# Speed_Bag_Counter-v10.net
KiCad netlist of a schematic drawn in EAGLE
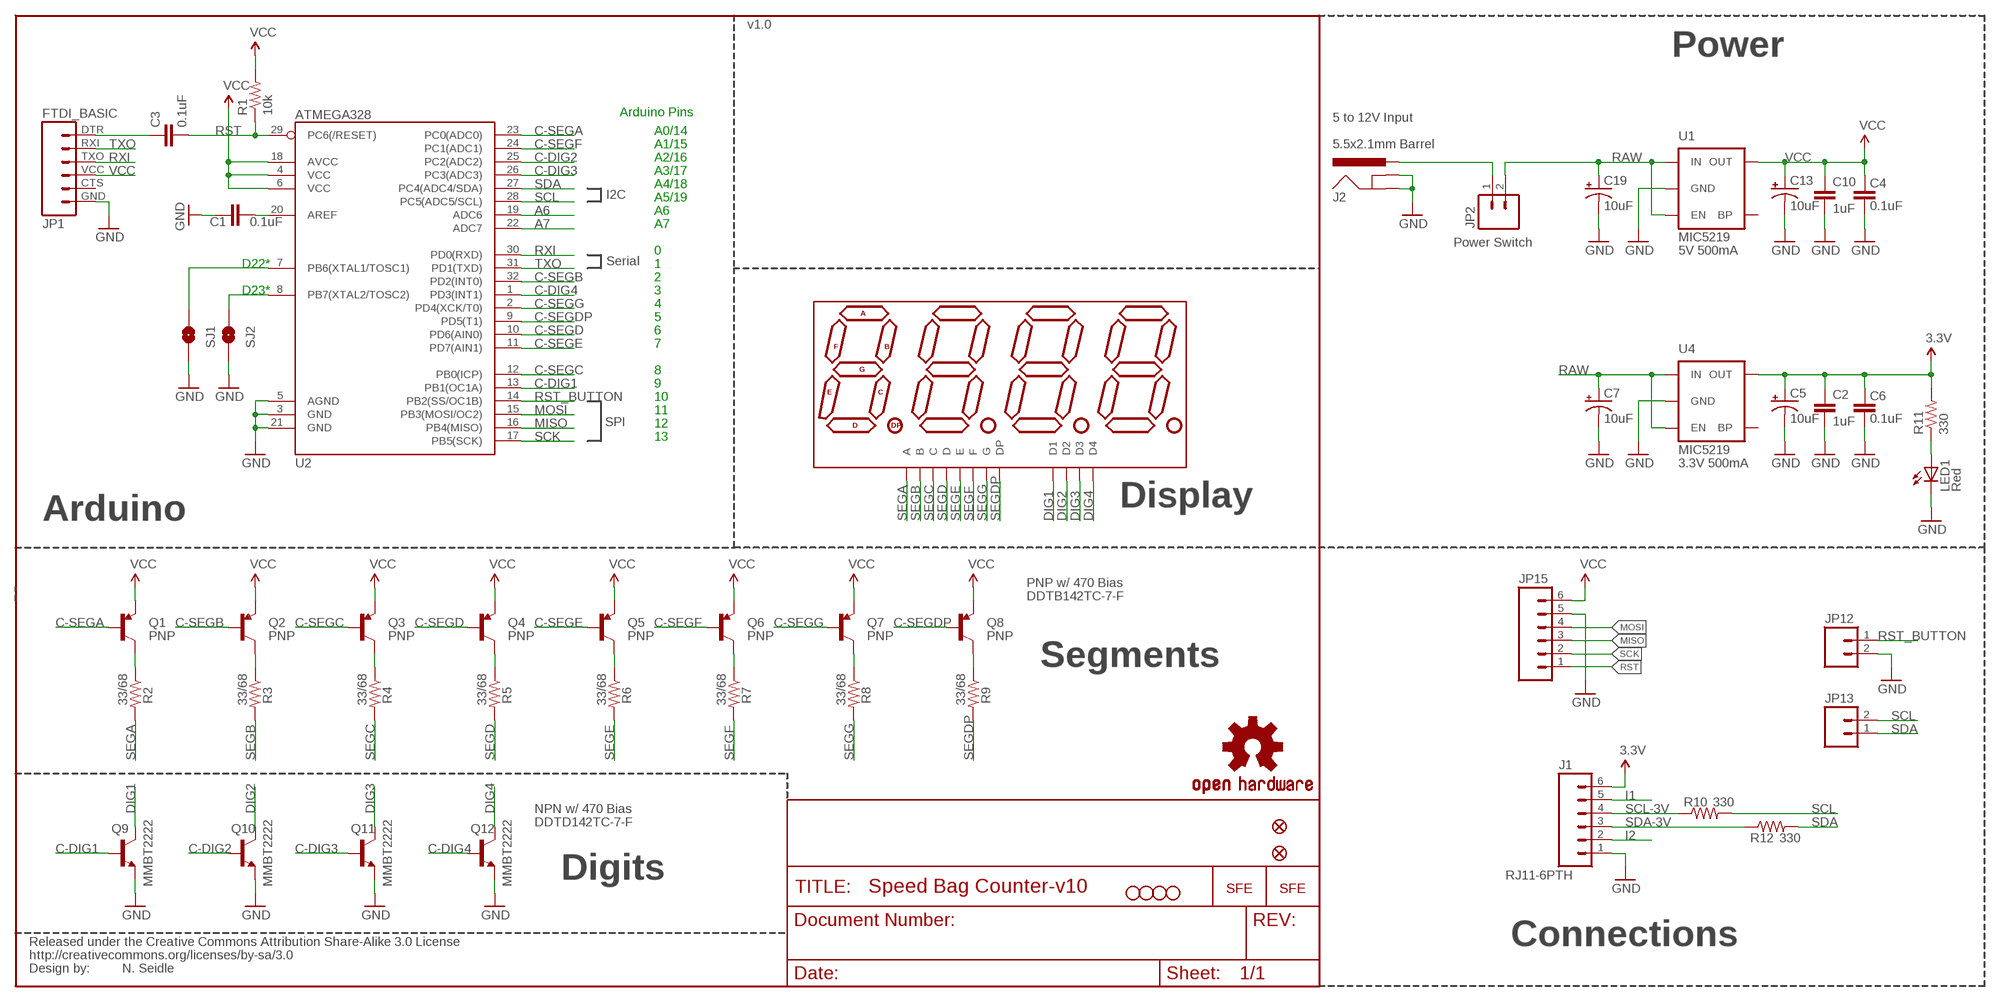
[diagram p0: schematic, sheet 1]

(export (version "E")
  (design (tool "Eeschema 10.0.6"))
  (components
    (comp (ref "C1")
      (value "0.1uF")
      (footprint "eagle-import:0402-CAP")
      (libsource (lib "eagle-import") (part "CAP0402-CAP"))
    )
    (comp (ref "C2")
      (value "1uF")
      (footprint "eagle-import:0402-CAP")
      (libsource (lib "eagle-import") (part "CAP0402-CAP"))
    )
    (comp (ref "C3")
      (value "0.1uF")
      (footprint "eagle-import:0402-CAP")
      (libsource (lib "eagle-import") (part "CAP0402-CAP"))
    )
    (comp (ref "C4")
      (value "0.1uF")
      (footprint "eagle-import:0402-CAP")
      (libsource (lib "eagle-import") (part "CAP0402-CAP"))
    )
    (comp (ref "C5")
      (value "10uF")
      (footprint "eagle-import:EIA3216")
      (libsource (lib "eagle-import") (part "CAP_POL1206"))
    )
    (comp (ref "C6")
      (value "0.1uF")
      (footprint "eagle-import:0402-CAP")
      (libsource (lib "eagle-import") (part "CAP0402-CAP"))
    )
    (comp (ref "C7")
      (value "10uF")
      (footprint "eagle-import:EIA3216")
      (libsource (lib "eagle-import") (part "CAP_POL1206"))
    )
    (comp (ref "C10")
      (value "1uF")
      (footprint "eagle-import:0402-CAP")
      (libsource (lib "eagle-import") (part "CAP0402-CAP"))
    )
    (comp (ref "C13")
      (value "10uF")
      (footprint "eagle-import:EIA3216")
      (libsource (lib "eagle-import") (part "CAP_POL1206"))
    )
    (comp (ref "C19")
      (value "10uF")
      (footprint "eagle-import:EIA3216")
      (libsource (lib "eagle-import") (part "CAP_POL1206"))
    )
    (comp (ref "J1")
      (value "RJ11-6PTH")
      (footprint "eagle-import:RJ11-6")
      (libsource (lib "eagle-import") (part "RJ11-6PTH"))
    )
    (comp (ref "J2")
      (value "5.5x2.1mm Barrel")
      (footprint "eagle-import:POWER_JACK_SMD")
      (libsource (lib "eagle-import") (part "POWER_JACKSMD"))
    )
    (comp (ref "JP1")
      (value "FTDI_BASIC")
      (footprint "eagle-import:FTDI_BASIC")
      (libsource (lib "eagle-import") (part "FTDI_BASICPTH"))
    )
    (comp (ref "JP2")
      (value "M02-JST-2MM-SMT")
      (footprint "eagle-import:JST-2-SMD")
      (libsource (lib "eagle-import") (part "M02-JST-2MM-SMT"))
    )
    (comp (ref "JP3")
      (value "STAND-OFF")
      (footprint "eagle-import:STAND-OFF")
      (libsource (lib "eagle-import") (part "STAND-OFF"))
    )
    (comp (ref "JP4")
      (value "STAND-OFF")
      (footprint "eagle-import:STAND-OFF")
      (libsource (lib "eagle-import") (part "STAND-OFF"))
    )
    (comp (ref "JP5")
      (value "STAND-OFF")
      (footprint "eagle-import:STAND-OFF")
      (libsource (lib "eagle-import") (part "STAND-OFF"))
    )
    (comp (ref "JP6")
      (value "STAND-OFF")
      (footprint "eagle-import:STAND-OFF")
      (libsource (lib "eagle-import") (part "STAND-OFF"))
    )
    (comp (ref "JP7")
      (value "FIDUCIALUFIDUCIAL")
      (footprint "eagle-import:MICRO-FIDUCIAL")
      (libsource (lib "eagle-import") (part "FIDUCIALUFIDUCIAL"))
    )
    (comp (ref "JP12")
      (value "M02-JST-2MM-SMT")
      (footprint "eagle-import:JST-2-SMD")
      (libsource (lib "eagle-import") (part "M02-JST-2MM-SMT"))
    )
    (comp (ref "JP13")
      (value "M02PTH")
      (footprint "eagle-import:1X02")
      (libsource (lib "eagle-import") (part "M02PTH"))
    )
    (comp (ref "JP14")
      (value "FIDUCIALUFIDUCIAL")
      (footprint "eagle-import:MICRO-FIDUCIAL")
      (libsource (lib "eagle-import") (part "FIDUCIALUFIDUCIAL"))
    )
    (comp (ref "JP15")
      (value "M06SIP")
      (footprint "eagle-import:1X06")
      (libsource (lib "eagle-import") (part "M06SIP"))
    )
    (comp (ref "LED1")
      (value "Red")
      (footprint "eagle-import:LED-0603")
      (libsource (lib "eagle-import") (part "LED0603"))
    )
    (comp (ref "Q1")
      (value "PNP")
      (footprint "eagle-import:SOT23-3")
      (libsource (lib "eagle-import") (part "TRANSISTOR_PNPSMD"))
    )
    (comp (ref "Q2")
      (value "PNP")
      (footprint "eagle-import:SOT23-3")
      (libsource (lib "eagle-import") (part "TRANSISTOR_PNPSMD"))
    )
    (comp (ref "Q3")
      (value "PNP")
      (footprint "eagle-import:SOT23-3")
      (libsource (lib "eagle-import") (part "TRANSISTOR_PNPSMD"))
    )
    (comp (ref "Q4")
      (value "PNP")
      (footprint "eagle-import:SOT23-3")
      (libsource (lib "eagle-import") (part "TRANSISTOR_PNPSMD"))
    )
    (comp (ref "Q5")
      (value "PNP")
      (footprint "eagle-import:SOT23-3")
      (libsource (lib "eagle-import") (part "TRANSISTOR_PNPSMD"))
    )
    (comp (ref "Q6")
      (value "PNP")
      (footprint "eagle-import:SOT23-3")
      (libsource (lib "eagle-import") (part "TRANSISTOR_PNPSMD"))
    )
    (comp (ref "Q7")
      (value "PNP")
      (footprint "eagle-import:SOT23-3")
      (libsource (lib "eagle-import") (part "TRANSISTOR_PNPSMD"))
    )
    (comp (ref "Q8")
      (value "PNP")
      (footprint "eagle-import:SOT23-3")
      (libsource (lib "eagle-import") (part "TRANSISTOR_PNPSMD"))
    )
    (comp (ref "Q9")
      (value "MMBT2222")
      (footprint "eagle-import:SOT23-3")
      (libsource (lib "eagle-import") (part "TRANSISTOR_NPNSOT23-3"))
    )
    (comp (ref "Q10")
      (value "MMBT2222")
      (footprint "eagle-import:SOT23-3")
      (libsource (lib "eagle-import") (part "TRANSISTOR_NPNSOT23-3"))
    )
    (comp (ref "Q11")
      (value "MMBT2222")
      (footprint "eagle-import:SOT23-3")
      (libsource (lib "eagle-import") (part "TRANSISTOR_NPNSOT23-3"))
    )
    (comp (ref "Q12")
      (value "MMBT2222")
      (footprint "eagle-import:SOT23-3")
      (libsource (lib "eagle-import") (part "TRANSISTOR_NPNSOT23-3"))
    )
    (comp (ref "R1")
      (value "10k")
      (footprint "eagle-import:0402-RES")
      (libsource (lib "eagle-import") (part "RESISTOR0402-RES"))
    )
    (comp (ref "R2")
      (value "33/68")
      (footprint "eagle-import:0402-RES")
      (libsource (lib "eagle-import") (part "RESISTOR0402-RES"))
    )
    (comp (ref "R3")
      (value "33/68")
      (footprint "eagle-import:0402-RES")
      (libsource (lib "eagle-import") (part "RESISTOR0402-RES"))
    )
    (comp (ref "R4")
      (value "33/68")
      (footprint "eagle-import:0402-RES")
      (libsource (lib "eagle-import") (part "RESISTOR0402-RES"))
    )
    (comp (ref "R5")
      (value "33/68")
      (footprint "eagle-import:0402-RES")
      (libsource (lib "eagle-import") (part "RESISTOR0402-RES"))
    )
    (comp (ref "R6")
      (value "33/68")
      (footprint "eagle-import:0402-RES")
      (libsource (lib "eagle-import") (part "RESISTOR0402-RES"))
    )
    (comp (ref "R7")
      (value "33/68")
      (footprint "eagle-import:0402-RES")
      (libsource (lib "eagle-import") (part "RESISTOR0402-RES"))
    )
    (comp (ref "R8")
      (value "33/68")
      (footprint "eagle-import:0402-RES")
      (libsource (lib "eagle-import") (part "RESISTOR0402-RES"))
    )
    (comp (ref "R9")
      (value "33/68")
      (footprint "eagle-import:0402-RES")
      (libsource (lib "eagle-import") (part "RESISTOR0402-RES"))
    )
    (comp (ref "R10")
      (value "330")
      (footprint "eagle-import:0402-RES")
      (libsource (lib "eagle-import") (part "RESISTOR0402-RES"))
    )
    (comp (ref "R11")
      (value "330")
      (footprint "eagle-import:0402-RES")
      (libsource (lib "eagle-import") (part "RESISTOR0402-RES"))
    )
    (comp (ref "R12")
      (value "330")
      (footprint "eagle-import:0402-RES")
      (libsource (lib "eagle-import") (part "RESISTOR0402-RES"))
    )
    (comp (ref "SJ1")
      (value "Counter Ctl")
      (footprint "eagle-import:SJ_2S-NO")
      (libsource (lib "eagle-import") (part "SOLDERJUMPERNO"))
    )
    (comp (ref "SJ2")
      (value "Counter Ctl")
      (footprint "eagle-import:SJ_2S-NO")
      (libsource (lib "eagle-import") (part "SOLDERJUMPERNO"))
    )
    (comp (ref "U$2")
      (value "LOGO-SFESK")
      (footprint "eagle-import:SFE-LOGO-FLAME")
      (libsource (lib "eagle-import") (part "LOGO-SFESK"))
    )
    (comp (ref "U$3")
      (value "CREATIVE_COMMONS")
      (footprint "eagle-import:CREATIVE_COMMONS")
      (libsource (lib "eagle-import") (part "CREATIVE_COMMONS"))
    )
    (comp (ref "U$4")
      (value "OSHW-LOGOS")
      (footprint "eagle-import:OSHW-LOGO-S")
      (libsource (lib "eagle-import") (part "OSHW-LOGOS"))
    )
    (comp (ref "U$7")
      (value "LOGO-SFENW2")
      (footprint "eagle-import:SFE-NEW-WEB")
      (libsource (lib "eagle-import") (part "LOGO-SFENW2"))
    )
    (comp (ref "U1")
      (value "MIC5219")
      (footprint "eagle-import:SOT23-5")
      (libsource (lib "eagle-import") (part "V_REG_LDOSMD"))
    )
    (comp (ref "U2")
      (value "ATMEGA328")
      (footprint "eagle-import:TQFP32-08")
      (libsource (lib "eagle-import") (part "ATMEGA168"))
    )
    (comp (ref "U3")
      (value "7-SEGMENT-4DIGIT-COUNTERPTH")
      (footprint "eagle-import:7-SEGMENT-4DIGIT-COUNTER")
      (libsource (lib "eagle-import") (part "7-SEGMENT-4DIGIT-COUNTERPTH"))
    )
    (comp (ref "U4")
      (value "MIC5219")
      (footprint "eagle-import:SOT23-5")
      (libsource (lib "eagle-import") (part "V_REG_LDOSMD"))
    )
  )
  (nets
    (net (code "1") (name "/A6") (class "Default")
      (node (ref "U2") (pin "19") (pinfunction "ADC6_19") (pintype "bidirectional"))
    )
    (net (code "2") (name "/A7") (class "Default")
      (node (ref "U2") (pin "22") (pinfunction "ADC7_22") (pintype "bidirectional"))
    )
    (net (code "3") (name "/C-DIG1") (class "Default")
      (node (ref "Q9") (pin "1") (pinfunction "B_1") (pintype "passive"))
      (node (ref "U2") (pin "13") (pinfunction "PB1(OC1A)_13") (pintype "bidirectional"))
    )
    (net (code "4") (name "/C-DIG2") (class "Default")
      (node (ref "Q10") (pin "1") (pinfunction "B_1") (pintype "passive"))
      (node (ref "U2") (pin "25") (pinfunction "PC2(ADC2)_25") (pintype "bidirectional"))
    )
    (net (code "5") (name "/C-DIG3") (class "Default")
      (node (ref "Q11") (pin "1") (pinfunction "B_1") (pintype "passive"))
      (node (ref "U2") (pin "26") (pinfunction "PC3(ADC3)_26") (pintype "bidirectional"))
    )
    (net (code "6") (name "/C-DIG4") (class "Default")
      (node (ref "Q12") (pin "1") (pinfunction "B_1") (pintype "passive"))
      (node (ref "U2") (pin "1") (pinfunction "PD3(INT1)_1") (pintype "bidirectional"))
    )
    (net (code "7") (name "/C-SEGA") (class "Default")
      (node (ref "Q1") (pin "1") (pinfunction "B_1") (pintype "passive"))
      (node (ref "U2") (pin "23") (pinfunction "PC0(ADC0)_23") (pintype "bidirectional"))
    )
    (net (code "8") (name "/C-SEGB") (class "Default")
      (node (ref "Q2") (pin "1") (pinfunction "B_1") (pintype "passive"))
      (node (ref "U2") (pin "32") (pinfunction "PD2(INT0)_32") (pintype "bidirectional"))
    )
    (net (code "9") (name "/C-SEGC") (class "Default")
      (node (ref "Q3") (pin "1") (pinfunction "B_1") (pintype "passive"))
      (node (ref "U2") (pin "12") (pinfunction "PB0(ICP)_12") (pintype "bidirectional"))
    )
    (net (code "10") (name "/C-SEGD") (class "Default")
      (node (ref "Q4") (pin "1") (pinfunction "B_1") (pintype "passive"))
      (node (ref "U2") (pin "10") (pinfunction "PD6(AIN0)_10") (pintype "bidirectional"))
    )
    (net (code "11") (name "/C-SEGDP") (class "Default")
      (node (ref "Q8") (pin "1") (pinfunction "B_1") (pintype "passive"))
      (node (ref "U2") (pin "9") (pinfunction "PD5(T1)_9") (pintype "bidirectional"))
    )
    (net (code "12") (name "/C-SEGE") (class "Default")
      (node (ref "Q5") (pin "1") (pinfunction "B_1") (pintype "passive"))
      (node (ref "U2") (pin "11") (pinfunction "PD7(AIN1)_11") (pintype "bidirectional"))
    )
    (net (code "13") (name "/C-SEGF") (class "Default")
      (node (ref "Q6") (pin "1") (pinfunction "B_1") (pintype "passive"))
      (node (ref "U2") (pin "24") (pinfunction "PC1(ADC1)_24") (pintype "bidirectional"))
    )
    (net (code "14") (name "/C-SEGG") (class "Default")
      (node (ref "Q7") (pin "1") (pinfunction "B_1") (pintype "passive"))
      (node (ref "U2") (pin "2") (pinfunction "PD4(XCK/T0)_2") (pintype "bidirectional"))
    )
    (net (code "15") (name "/DIG1") (class "Default")
      (node (ref "Q9") (pin "3") (pinfunction "C_3") (pintype "passive"))
      (node (ref "U3") (pin "12") (pinfunction "D1_12") (pintype "bidirectional"))
    )
    (net (code "16") (name "/DIG2") (class "Default")
      (node (ref "Q10") (pin "3") (pinfunction "C_3") (pintype "passive"))
      (node (ref "U3") (pin "9") (pinfunction "D2_9") (pintype "bidirectional"))
    )
    (net (code "17") (name "/DIG3") (class "Default")
      (node (ref "Q11") (pin "3") (pinfunction "C_3") (pintype "passive"))
      (node (ref "U3") (pin "8") (pinfunction "D3_8") (pintype "bidirectional"))
    )
    (net (code "18") (name "/DIG4") (class "Default")
      (node (ref "Q12") (pin "3") (pinfunction "C_3") (pintype "passive"))
      (node (ref "U3") (pin "6") (pinfunction "D4_6") (pintype "bidirectional"))
    )
    (net (code "19") (name "/I1") (class "Default")
      (node (ref "J1") (pin "5") (pinfunction "5_5") (pintype "passive"))
    )
    (net (code "20") (name "/I2") (class "Default")
      (node (ref "J1") (pin "2") (pinfunction "2_2") (pintype "passive"))
    )
    (net (code "21") (name "/RAW") (class "Default")
      (node (ref "C19") (pin "A") (pinfunction "+_A") (pintype "passive"))
      (node (ref "C7") (pin "A") (pinfunction "+_A") (pintype "passive"))
      (node (ref "JP2") (pin "2") (pinfunction "1_2") (pintype "passive"))
      (node (ref "U1") (pin "1") (pinfunction "IN_1") (pintype "input"))
      (node (ref "U1") (pin "3") (pinfunction "EN_3") (pintype "input"))
      (node (ref "U4") (pin "1") (pinfunction "IN_1") (pintype "input"))
      (node (ref "U4") (pin "3") (pinfunction "EN_3") (pintype "input"))
    )
    (net (code "22") (name "/RST_BUTTON") (class "Default")
      (node (ref "JP12") (pin "1") (pinfunction "2_1") (pintype "passive"))
      (node (ref "U2") (pin "14") (pinfunction "PB2(SS/OC1B)_14") (pintype "bidirectional"))
    )
    (net (code "23") (name "/RXI") (class "Default")
      (node (ref "JP1") (pin "TXO") (pinfunction "3_TXO") (pintype "passive"))
      (node (ref "U2") (pin "30") (pinfunction "PD0(RXD)_30") (pintype "bidirectional"))
    )
    (net (code "24") (name "/SCL") (class "Default")
      (node (ref "JP13") (pin "2") (pinfunction "2_2") (pintype "passive"))
      (node (ref "R10") (pin "2") (pinfunction "2_2") (pintype "passive"))
      (node (ref "U2") (pin "28") (pinfunction "PC5(ADC5/SCL)_28") (pintype "bidirectional"))
    )
    (net (code "25") (name "/SCL-3V") (class "Default")
      (node (ref "J1") (pin "4") (pinfunction "4_4") (pintype "passive"))
      (node (ref "R10") (pin "1") (pinfunction "1_1") (pintype "passive"))
    )
    (net (code "26") (name "/SDA") (class "Default")
      (node (ref "JP13") (pin "1") (pinfunction "1_1") (pintype "passive"))
      (node (ref "R12") (pin "2") (pinfunction "2_2") (pintype "passive"))
      (node (ref "U2") (pin "27") (pinfunction "PC4(ADC4/SDA)_27") (pintype "bidirectional"))
    )
    (net (code "27") (name "/SDA-3V") (class "Default")
      (node (ref "J1") (pin "3") (pinfunction "3_3") (pintype "passive"))
      (node (ref "R12") (pin "1") (pinfunction "1_1") (pintype "passive"))
    )
    (net (code "28") (name "/SEGA") (class "Default")
      (node (ref "R2") (pin "2") (pinfunction "2_2") (pintype "passive"))
      (node (ref "U3") (pin "11") (pinfunction "A_11") (pintype "bidirectional"))
    )
    (net (code "29") (name "/SEGB") (class "Default")
      (node (ref "R3") (pin "2") (pinfunction "2_2") (pintype "passive"))
      (node (ref "U3") (pin "7") (pinfunction "B_7") (pintype "bidirectional"))
    )
    (net (code "30") (name "/SEGC") (class "Default")
      (node (ref "R4") (pin "2") (pinfunction "2_2") (pintype "passive"))
      (node (ref "U3") (pin "4") (pinfunction "C_4") (pintype "bidirectional"))
    )
    (net (code "31") (name "/SEGD") (class "Default")
      (node (ref "R5") (pin "2") (pinfunction "2_2") (pintype "passive"))
      (node (ref "U3") (pin "2") (pinfunction "D_2") (pintype "bidirectional"))
    )
    (net (code "32") (name "/SEGDP") (class "Default")
      (node (ref "R9") (pin "2") (pinfunction "2_2") (pintype "passive"))
      (node (ref "U3") (pin "3") (pinfunction "DP_3") (pintype "bidirectional"))
    )
    (net (code "33") (name "/SEGE") (class "Default")
      (node (ref "R6") (pin "2") (pinfunction "2_2") (pintype "passive"))
      (node (ref "U3") (pin "1") (pinfunction "E_1") (pintype "bidirectional"))
    )
    (net (code "34") (name "/SEGF") (class "Default")
      (node (ref "R7") (pin "2") (pinfunction "2_2") (pintype "passive"))
      (node (ref "U3") (pin "10") (pinfunction "F_10") (pintype "bidirectional"))
    )
    (net (code "35") (name "/SEGG") (class "Default")
      (node (ref "R8") (pin "2") (pinfunction "2_2") (pintype "passive"))
      (node (ref "U3") (pin "5") (pinfunction "G_5") (pintype "bidirectional"))
    )
    (net (code "36") (name "/TXO") (class "Default")
      (node (ref "JP1") (pin "RXI") (pinfunction "2_RXI") (pintype "passive"))
      (node (ref "U2") (pin "31") (pinfunction "PD1(TXD)_31") (pintype "bidirectional"))
    )
    (net (code "37") (name "3.3V") (class "Default")
      (node (ref "C2") (pin "1") (pinfunction "1_1") (pintype "passive"))
      (node (ref "C5") (pin "A") (pinfunction "+_A") (pintype "passive"))
      (node (ref "C6") (pin "2") (pinfunction "2_2") (pintype "passive"))
      (node (ref "J1") (pin "6") (pinfunction "6_6") (pintype "passive"))
      (node (ref "R11") (pin "2") (pinfunction "2_2") (pintype "passive"))
      (node (ref "U4") (pin "5") (pinfunction "OUT_5") (pintype "passive"))
    )
    (net (code "38") (name "GND") (class "Default")
      (node (ref "C1") (pin "1") (pinfunction "1_1") (pintype "passive"))
      (node (ref "C10") (pin "2") (pinfunction "2_2") (pintype "passive"))
      (node (ref "C13") (pin "C") (pinfunction "-_C") (pintype "passive"))
      (node (ref "C19") (pin "C") (pinfunction "-_C") (pintype "passive"))
      (node (ref "C2") (pin "2") (pinfunction "2_2") (pintype "passive"))
      (node (ref "C4") (pin "1") (pinfunction "1_1") (pintype "passive"))
      (node (ref "C5") (pin "C") (pinfunction "-_C") (pintype "passive"))
      (node (ref "C6") (pin "1") (pinfunction "1_1") (pintype "passive"))
      (node (ref "C7") (pin "C") (pinfunction "-_C") (pintype "passive"))
      (node (ref "J1") (pin "1") (pinfunction "1_1") (pintype "passive"))
      (node (ref "J2") (pin "GND") (pinfunction "GNDBREAK_GND") (pintype "bidirectional"))
      (node (ref "J2") (pin "P$4") (pinfunction "GND_P$4") (pintype "bidirectional"))
      (node (ref "JP1") (pin "GND") (pinfunction "6_GND") (pintype "passive"))
      (node (ref "JP12") (pin "2") (pinfunction "1_2") (pintype "passive"))
      (node (ref "JP15") (pin "5") (pinfunction "5_5") (pintype "passive"))
      (node (ref "LED1") (pin "C") (pinfunction "C_C") (pintype "passive"))
      (node (ref "Q10") (pin "2") (pinfunction "E_2") (pintype "passive"))
      (node (ref "Q11") (pin "2") (pinfunction "E_2") (pintype "passive"))
      (node (ref "Q12") (pin "2") (pinfunction "E_2") (pintype "passive"))
      (node (ref "Q9") (pin "2") (pinfunction "E_2") (pintype "passive"))
      (node (ref "SJ1") (pin "2") (pinfunction "2_2") (pintype "passive"))
      (node (ref "SJ2") (pin "2") (pinfunction "2_2") (pintype "passive"))
      (node (ref "U1") (pin "2") (pinfunction "GND_2") (pintype "input"))
      (node (ref "U2") (pin "21") (pinfunction "GND_21") (pintype "bidirectional"))
      (node (ref "U2") (pin "3") (pinfunction "GND_3") (pintype "bidirectional"))
      (node (ref "U2") (pin "5") (pinfunction "AGND_5") (pintype "bidirectional"))
      (node (ref "U4") (pin "2") (pinfunction "GND_2") (pintype "input"))
    )
    (net (code "39") (name "MISO") (class "Default")
      (node (ref "JP15") (pin "3") (pinfunction "3_3") (pintype "passive"))
      (node (ref "U2") (pin "16") (pinfunction "PB4(MISO)_16") (pintype "bidirectional"))
    )
    (net (code "40") (name "MOSI") (class "Default")
      (node (ref "JP15") (pin "4") (pinfunction "4_4") (pintype "passive"))
      (node (ref "U2") (pin "15") (pinfunction "PB3(MOSI/OC2)_15") (pintype "bidirectional"))
    )
    (net (code "41") (name "Net-(J2-PWR)") (class "Default")
      (node (ref "J2") (pin "VIN0") (pinfunction "PWR_VIN0") (pintype "bidirectional"))
      (node (ref "JP2") (pin "1") (pinfunction "2_1") (pintype "passive"))
    )
    (net (code "42") (name "Net-(JP1-1)") (class "Default")
      (node (ref "C3") (pin "1") (pinfunction "1_1") (pintype "passive"))
      (node (ref "JP1") (pin "DTR") (pinfunction "1_DTR") (pintype "passive"))
    )
    (net (code "43") (name "Net-(LED1-PadA)") (class "Default")
      (node (ref "LED1") (pin "A") (pinfunction "A_A") (pintype "passive"))
      (node (ref "R11") (pin "1") (pinfunction "1_1") (pintype "passive"))
    )
    (net (code "44") (name "Net-(Q1-C)") (class "Default")
      (node (ref "Q1") (pin "3") (pinfunction "C_3") (pintype "passive"))
      (node (ref "R2") (pin "1") (pinfunction "1_1") (pintype "passive"))
    )
    (net (code "45") (name "Net-(Q2-C)") (class "Default")
      (node (ref "Q2") (pin "3") (pinfunction "C_3") (pintype "passive"))
      (node (ref "R3") (pin "1") (pinfunction "1_1") (pintype "passive"))
    )
    (net (code "46") (name "Net-(Q3-C)") (class "Default")
      (node (ref "Q3") (pin "3") (pinfunction "C_3") (pintype "passive"))
      (node (ref "R4") (pin "1") (pinfunction "1_1") (pintype "passive"))
    )
    (net (code "47") (name "Net-(Q4-C)") (class "Default")
      (node (ref "Q4") (pin "3") (pinfunction "C_3") (pintype "passive"))
      (node (ref "R5") (pin "1") (pinfunction "1_1") (pintype "passive"))
    )
    (net (code "48") (name "Net-(Q5-C)") (class "Default")
      (node (ref "Q5") (pin "3") (pinfunction "C_3") (pintype "passive"))
      (node (ref "R6") (pin "1") (pinfunction "1_1") (pintype "passive"))
    )
    (net (code "49") (name "Net-(Q6-C)") (class "Default")
      (node (ref "Q6") (pin "3") (pinfunction "C_3") (pintype "passive"))
      (node (ref "R7") (pin "1") (pinfunction "1_1") (pintype "passive"))
    )
    (net (code "50") (name "Net-(Q7-C)") (class "Default")
      (node (ref "Q7") (pin "3") (pinfunction "C_3") (pintype "passive"))
      (node (ref "R8") (pin "1") (pinfunction "1_1") (pintype "passive"))
    )
    (net (code "51") (name "Net-(Q8-C)") (class "Default")
      (node (ref "Q8") (pin "3") (pinfunction "C_3") (pintype "passive"))
      (node (ref "R9") (pin "1") (pinfunction "1_1") (pintype "passive"))
    )
    (net (code "52") (name "Net-(U2-AREF)") (class "Default")
      (node (ref "C1") (pin "2") (pinfunction "2_2") (pintype "passive"))
      (node (ref "U2") (pin "20") (pinfunction "AREF_20") (pintype "bidirectional"))
    )
    (net (code "53") (name "Net-(U2-PB6(XTAL1{slash}TOSC1))") (class "Default")
      (node (ref "SJ1") (pin "1") (pinfunction "1_1") (pintype "passive"))
      (node (ref "U2") (pin "7") (pinfunction "PB6(XTAL1/TOSC1)_7") (pintype "bidirectional"))
    )
    (net (code "54") (name "Net-(U2-PB7(XTAL2{slash}TOSC2))") (class "Default")
      (node (ref "SJ2") (pin "1") (pinfunction "1_1") (pintype "passive"))
      (node (ref "U2") (pin "8") (pinfunction "PB7(XTAL2/TOSC2)_8") (pintype "bidirectional"))
    )
    (net (code "55") (name "RST") (class "Default")
      (node (ref "C3") (pin "2") (pinfunction "2_2") (pintype "passive"))
      (node (ref "JP15") (pin "1") (pinfunction "1_1") (pintype "passive"))
      (node (ref "R1") (pin "1") (pinfunction "1_1") (pintype "passive"))
      (node (ref "U2") (pin "29") (pinfunction "PC6(/RESET)_29") (pintype "bidirectional"))
    )
    (net (code "56") (name "SCK") (class "Default")
      (node (ref "JP15") (pin "2") (pinfunction "2_2") (pintype "passive"))
      (node (ref "U2") (pin "17") (pinfunction "PB5(SCK)_17") (pintype "bidirectional"))
    )
    (net (code "57") (name "VCC") (class "Default")
      (node (ref "C10") (pin "1") (pinfunction "1_1") (pintype "passive"))
      (node (ref "C13") (pin "A") (pinfunction "+_A") (pintype "passive"))
      (node (ref "C4") (pin "2") (pinfunction "2_2") (pintype "passive"))
      (node (ref "JP1") (pin "VCC") (pinfunction "4_VCC") (pintype "passive"))
      (node (ref "JP15") (pin "6") (pinfunction "6_6") (pintype "passive"))
      (node (ref "Q1") (pin "2") (pinfunction "E_2") (pintype "passive"))
      (node (ref "Q2") (pin "2") (pinfunction "E_2") (pintype "passive"))
      (node (ref "Q3") (pin "2") (pinfunction "E_2") (pintype "passive"))
      (node (ref "Q4") (pin "2") (pinfunction "E_2") (pintype "passive"))
      (node (ref "Q5") (pin "2") (pinfunction "E_2") (pintype "passive"))
      (node (ref "Q6") (pin "2") (pinfunction "E_2") (pintype "passive"))
      (node (ref "Q7") (pin "2") (pinfunction "E_2") (pintype "passive"))
      (node (ref "Q8") (pin "2") (pinfunction "E_2") (pintype "passive"))
      (node (ref "R1") (pin "2") (pinfunction "2_2") (pintype "passive"))
      (node (ref "U1") (pin "5") (pinfunction "OUT_5") (pintype "passive"))
      (node (ref "U2") (pin "18") (pinfunction "AVCC_18") (pintype "bidirectional"))
      (node (ref "U2") (pin "4") (pinfunction "VCC_4") (pintype "bidirectional"))
      (node (ref "U2") (pin "6") (pinfunction "VCC_6") (pintype "bidirectional"))
    )
    (net (code "58") (name "unconnected-(JP1-5-PadCTS)") (class "Default")
      (node (ref "JP1") (pin "CTS") (pinfunction "5_CTS") (pintype "passive"))
    )
    (net (code "59") (name "unconnected-(U1-BP-Pad4)") (class "Default")
      (node (ref "U1") (pin "4") (pinfunction "BP_4") (pintype "input"))
    )
    (net (code "60") (name "unconnected-(U4-BP-Pad4)") (class "Default")
      (node (ref "U4") (pin "4") (pinfunction "BP_4") (pintype "input"))
    )
  )
)
